# WASP-PCB-WDT-F1R0.net
KiCad netlist of a schematic drawn in EAGLE
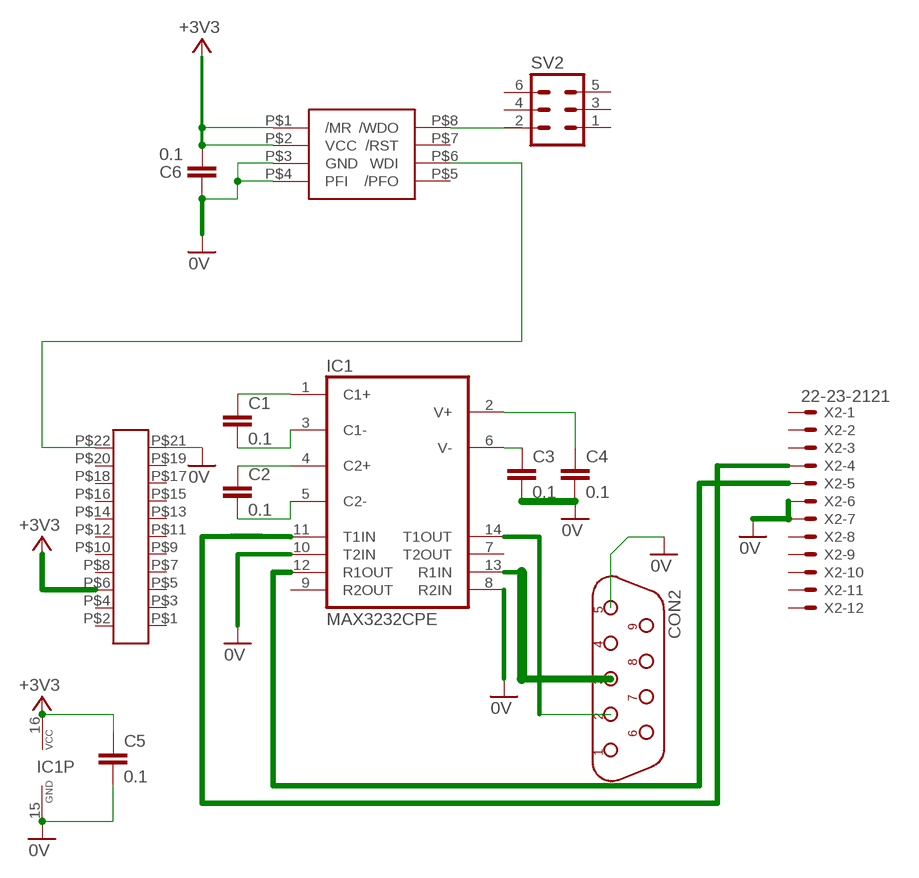
[diagram p0: schematic, sheet 1]

(export (version "E")
  (design (tool "Eeschema 10.0.6"))
  (components
    (comp (ref "C1")
      (value "0.1")
      (footprint "eagle-import:C5B2.5")
      (libsource (lib "eagle-import") (part "C5/2.5"))
    )
    (comp (ref "C2")
      (value "0.1")
      (footprint "eagle-import:C5B2.5")
      (libsource (lib "eagle-import") (part "C5/2.5"))
    )
    (comp (ref "C3")
      (value "0.1")
      (footprint "eagle-import:C5B2.5")
      (libsource (lib "eagle-import") (part "C5/2.5"))
    )
    (comp (ref "C4")
      (value "0.1")
      (footprint "eagle-import:C5B2.5")
      (libsource (lib "eagle-import") (part "C5/2.5"))
    )
    (comp (ref "C5")
      (value "0.1")
      (footprint "eagle-import:C5B2.5")
      (libsource (lib "eagle-import") (part "C5/2.5"))
    )
    (comp (ref "C6")
      (value "0.1")
      (footprint "eagle-import:C5B2.5")
      (libsource (lib "eagle-import") (part "C5/2.5"))
    )
    (comp (ref "CON2")
      (value "CONNECT_DB9F/90")
      (footprint "eagle-import:CONNECT_D-09F_90")
      (libsource (lib "eagle-import") (part "CONNECT_DB9F/90"))
    )
    (comp (ref "IC1")
      (value "MAX3232CPE")
      (footprint "eagle-import:DIL16")
      (fields (field (name "MF") "MAXIM") (field (name "MPN") "MAX3232CPE+"))
      (libsource (lib "eagle-import") (part "MAX3232PEC"))
    )
    (comp (ref "SV2")
      (value "CON-ML_ML6")
      (footprint "eagle-import:CON-ML_ML6")
      (libsource (lib "eagle-import") (part "CON-ML_ML6"))
    )
    (comp (ref "U$2")
      (value "ML22PML22P-PKG")
      (footprint "eagle-import:CON-ML-22P")
      (libsource (lib "eagle-import") (part "ML22PML22P-PKG"))
    )
    (comp (ref "U$3")
      (value "ADM706P")
      (footprint "eagle-import:ADM706P")
      (libsource (lib "eagle-import") (part "ADM706P"))
    )
    (comp (ref "X2")
      (value "22-23-2121")
      (footprint "eagle-import:22-23-2121")
      (fields (field (name "MF") "MOLEX"))
      (libsource (lib "eagle-import") (part "22-23-2121"))
    )
  )
  (nets
    (net (code "1") (name "+3V3") (class "Default")
      (node (ref "C5") (pin "1") (pinfunction "1_1") (pintype "passive"))
      (node (ref "C6") (pin "1") (pinfunction "1_1") (pintype "passive"))
      (node (ref "IC1") (pin "16") (pinfunction "VCC_16") (pintype "power_in"))
      (node (ref "U$2") (pin "P$6") (pinfunction "6_P$6") (pintype "passive"))
      (node (ref "U$3") (pin "P$1") (pinfunction "/MR_P$1") (pintype "input"))
      (node (ref "U$3") (pin "P$2") (pinfunction "VCC_P$2") (pintype "power_in"))
    )
    (net (code "2") (name "/14") (class "Default")
      (node (ref "U$2") (pin "P$14") (pinfunction "14_P$14") (pintype "power_in"))
    )
    (net (code "3") (name "0V") (class "Default")
      (node (ref "C3") (pin "2") (pinfunction "2_2") (pintype "passive"))
      (node (ref "C4") (pin "2") (pinfunction "2_2") (pintype "passive"))
      (node (ref "C5") (pin "2") (pinfunction "2_2") (pintype "passive"))
      (node (ref "C6") (pin "2") (pinfunction "2_2") (pintype "passive"))
      (node (ref "CON2") (pin "5") (pinfunction "5_5") (pintype "passive"))
      (node (ref "IC1") (pin "10") (pinfunction "T2IN_10") (pintype "input"))
      (node (ref "IC1") (pin "15") (pinfunction "GND_15") (pintype "power_in"))
      (node (ref "IC1") (pin "8") (pinfunction "R2IN_8") (pintype "input"))
      (node (ref "U$2") (pin "P$21") (pinfunction "21_P$21") (pintype "passive"))
      (node (ref "U$3") (pin "P$3") (pinfunction "GND_P$3") (pintype "power_in"))
      (node (ref "U$3") (pin "P$4") (pinfunction "PFI_P$4") (pintype "input"))
      (node (ref "X2") (pin "6") (pinfunction "S_6") (pintype "passive"))
      (node (ref "X2") (pin "7") (pinfunction "S_7") (pintype "passive"))
    )
    (net (code "4") (name "Net-(IC1A-C1+)") (class "Default")
      (node (ref "C1") (pin "1") (pinfunction "1_1") (pintype "passive"))
      (node (ref "IC1") (pin "1") (pinfunction "C1+_1") (pintype "bidirectional"))
    )
    (net (code "5") (name "Net-(IC1A-C1-)") (class "Default")
      (node (ref "C1") (pin "2") (pinfunction "2_2") (pintype "passive"))
      (node (ref "IC1") (pin "3") (pinfunction "C1-_3") (pintype "bidirectional"))
    )
    (net (code "6") (name "Net-(IC1A-C2+)") (class "Default")
      (node (ref "C2") (pin "1") (pinfunction "1_1") (pintype "passive"))
      (node (ref "IC1") (pin "4") (pinfunction "C2+_4") (pintype "bidirectional"))
    )
    (net (code "7") (name "Net-(IC1A-C2-)") (class "Default")
      (node (ref "C2") (pin "2") (pinfunction "2_2") (pintype "passive"))
      (node (ref "IC1") (pin "5") (pinfunction "C2-_5") (pintype "bidirectional"))
    )
    (net (code "8") (name "Net-(IC1A-R1IN)") (class "Default")
      (node (ref "CON2") (pin "3") (pinfunction "3_3") (pintype "passive"))
      (node (ref "IC1") (pin "13") (pinfunction "R1IN_13") (pintype "input"))
    )
    (net (code "9") (name "Net-(IC1A-R1OUT)") (class "Default")
      (node (ref "IC1") (pin "12") (pinfunction "R1OUT_12") (pintype "output"))
      (node (ref "X2") (pin "5") (pinfunction "S_5") (pintype "passive"))
    )
    (net (code "10") (name "Net-(IC1A-T1IN)") (class "Default")
      (node (ref "IC1") (pin "11") (pinfunction "T1IN_11") (pintype "input"))
      (node (ref "X2") (pin "4") (pinfunction "S_4") (pintype "passive"))
    )
    (net (code "11") (name "Net-(IC1A-T1OUT)") (class "Default")
      (node (ref "CON2") (pin "2") (pinfunction "2_2") (pintype "passive"))
      (node (ref "IC1") (pin "14") (pinfunction "T1OUT_14") (pintype "output"))
    )
    (net (code "12") (name "Net-(IC1A-V+)") (class "Default")
      (node (ref "C4") (pin "1") (pinfunction "1_1") (pintype "passive"))
      (node (ref "IC1") (pin "2") (pinfunction "V+_2") (pintype "bidirectional"))
    )
    (net (code "13") (name "Net-(IC1A-V-)") (class "Default")
      (node (ref "C3") (pin "1") (pinfunction "1_1") (pintype "passive"))
      (node (ref "IC1") (pin "6") (pinfunction "V-_6") (pintype "bidirectional"))
    )
    (net (code "14") (name "Net-(U$2-22)") (class "Default")
      (node (ref "U$2") (pin "P$22") (pinfunction "22_P$22") (pintype "passive"))
      (node (ref "U$3") (pin "P$6") (pinfunction "WDI_P$6") (pintype "input"))
    )
    (net (code "15") (name "Net-(U$3-{slash}WDO)") (class "Default")
      (node (ref "SV2") (pin "2") (pinfunction "2_2") (pintype "passive"))
      (node (ref "U$3") (pin "P$8") (pinfunction "/WDO_P$8") (pintype "output"))
    )
    (net (code "16") (name "unconnected-(CON2-Pad1)") (class "Default")
      (node (ref "CON2") (pin "1") (pinfunction "1_1") (pintype "passive"))
    )
    (net (code "17") (name "unconnected-(CON2-Pad4)") (class "Default")
      (node (ref "CON2") (pin "4") (pinfunction "4_4") (pintype "passive"))
    )
    (net (code "18") (name "unconnected-(CON2-Pad6)") (class "Default")
      (node (ref "CON2") (pin "6") (pinfunction "6_6") (pintype "passive"))
    )
    (net (code "19") (name "unconnected-(CON2-Pad7)") (class "Default")
      (node (ref "CON2") (pin "7") (pinfunction "7_7") (pintype "passive"))
    )
    (net (code "20") (name "unconnected-(CON2-Pad8)") (class "Default")
      (node (ref "CON2") (pin "8") (pinfunction "8_8") (pintype "passive"))
    )
    (net (code "21") (name "unconnected-(CON2-Pad9)") (class "Default")
      (node (ref "CON2") (pin "9") (pinfunction "9_9") (pintype "passive"))
    )
    (net (code "22") (name "unconnected-(IC1A-R2OUT-Pad9)") (class "Default")
      (node (ref "IC1") (pin "9") (pinfunction "R2OUT_9") (pintype "output"))
    )
    (net (code "23") (name "unconnected-(IC1A-T2OUT-Pad7)") (class "Default")
      (node (ref "IC1") (pin "7") (pinfunction "T2OUT_7") (pintype "output"))
    )
    (net (code "24") (name "unconnected-(SV2-Pad1)") (class "Default")
      (node (ref "SV2") (pin "1") (pinfunction "1_1") (pintype "passive"))
    )
    (net (code "25") (name "unconnected-(SV2-Pad3)") (class "Default")
      (node (ref "SV2") (pin "3") (pinfunction "3_3") (pintype "passive"))
    )
    (net (code "26") (name "unconnected-(SV2-Pad4)") (class "Default")
      (node (ref "SV2") (pin "4") (pinfunction "4_4") (pintype "passive"))
    )
    (net (code "27") (name "unconnected-(SV2-Pad5)") (class "Default")
      (node (ref "SV2") (pin "5") (pinfunction "5_5") (pintype "passive"))
    )
    (net (code "28") (name "unconnected-(SV2-Pad6)") (class "Default")
      (node (ref "SV2") (pin "6") (pinfunction "6_6") (pintype "passive"))
    )
    (net (code "29") (name "unconnected-(U$2-1-PadP$1)") (class "Default")
      (node (ref "U$2") (pin "P$1") (pinfunction "1_P$1") (pintype "passive"))
    )
    (net (code "30") (name "unconnected-(U$2-2-PadP$2)") (class "Default")
      (node (ref "U$2") (pin "P$2") (pinfunction "2_P$2") (pintype "passive"))
    )
    (net (code "31") (name "unconnected-(U$2-3-PadP$3)") (class "Default")
      (node (ref "U$2") (pin "P$3") (pinfunction "3_P$3") (pintype "passive"))
    )
    (net (code "32") (name "unconnected-(U$2-4-PadP$4)") (class "Default")
      (node (ref "U$2") (pin "P$4") (pinfunction "4_P$4") (pintype "passive"))
    )
    (net (code "33") (name "unconnected-(U$2-5-PadP$5)") (class "Default")
      (node (ref "U$2") (pin "P$5") (pinfunction "5_P$5") (pintype "passive"))
    )
    (net (code "34") (name "unconnected-(U$2-7-PadP$7)") (class "Default")
      (node (ref "U$2") (pin "P$7") (pinfunction "7_P$7") (pintype "passive"))
    )
    (net (code "35") (name "unconnected-(U$2-8-PadP$8)") (class "Default")
      (node (ref "U$2") (pin "P$8") (pinfunction "8_P$8") (pintype "passive"))
    )
    (net (code "36") (name "unconnected-(U$2-9-PadP$9)") (class "Default")
      (node (ref "U$2") (pin "P$9") (pinfunction "9_P$9") (pintype "passive"))
    )
    (net (code "37") (name "unconnected-(U$2-10-PadP$10)") (class "Default")
      (node (ref "U$2") (pin "P$10") (pinfunction "10_P$10") (pintype "passive"))
    )
    (net (code "38") (name "unconnected-(U$2-11-PadP$11)") (class "Default")
      (node (ref "U$2") (pin "P$11") (pinfunction "11_P$11") (pintype "passive"))
    )
    (net (code "39") (name "unconnected-(U$2-12-PadP$12)") (class "Default")
      (node (ref "U$2") (pin "P$12") (pinfunction "12_P$12") (pintype "passive"))
    )
    (net (code "40") (name "unconnected-(U$2-13-PadP$13)") (class "Default")
      (node (ref "U$2") (pin "P$13") (pinfunction "13_P$13") (pintype "passive"))
    )
    (net (code "41") (name "unconnected-(U$2-15-PadP$15)") (class "Default")
      (node (ref "U$2") (pin "P$15") (pinfunction "15_P$15") (pintype "passive"))
    )
    (net (code "42") (name "unconnected-(U$2-16-PadP$16)") (class "Default")
      (node (ref "U$2") (pin "P$16") (pinfunction "16_P$16") (pintype "passive"))
    )
    (net (code "43") (name "unconnected-(U$2-17-PadP$17)") (class "Default")
      (node (ref "U$2") (pin "P$17") (pinfunction "17_P$17") (pintype "passive"))
    )
    (net (code "44") (name "unconnected-(U$2-18-PadP$18)") (class "Default")
      (node (ref "U$2") (pin "P$18") (pinfunction "18_P$18") (pintype "passive"))
    )
    (net (code "45") (name "unconnected-(U$2-19-PadP$19)") (class "Default")
      (node (ref "U$2") (pin "P$19") (pinfunction "19_P$19") (pintype "passive"))
    )
    (net (code "46") (name "unconnected-(U$2-20-PadP$20)") (class "Default")
      (node (ref "U$2") (pin "P$20") (pinfunction "20_P$20") (pintype "passive"))
    )
    (net (code "47") (name "unconnected-(U$3-{slash}PFO-PadP$5)") (class "Default")
      (node (ref "U$3") (pin "P$5") (pinfunction "/PFO_P$5") (pintype "output"))
    )
    (net (code "48") (name "unconnected-(U$3-{slash}RST-PadP$7)") (class "Default")
      (node (ref "U$3") (pin "P$7") (pinfunction "/RST_P$7") (pintype "output"))
    )
    (net (code "49") (name "unconnected-(X2A-S-Pad1)") (class "Default")
      (node (ref "X2") (pin "1") (pinfunction "S_1") (pintype "passive"))
    )
    (net (code "50") (name "unconnected-(X2B-S-Pad10)") (class "Default")
      (node (ref "X2") (pin "10") (pinfunction "S_10") (pintype "passive"))
    )
    (net (code "51") (name "unconnected-(X2C-S-Pad11)") (class "Default")
      (node (ref "X2") (pin "11") (pinfunction "S_11") (pintype "passive"))
    )
    (net (code "52") (name "unconnected-(X2D-S-Pad12)") (class "Default")
      (node (ref "X2") (pin "12") (pinfunction "S_12") (pintype "passive"))
    )
    (net (code "53") (name "unconnected-(X2E-S-Pad2)") (class "Default")
      (node (ref "X2") (pin "2") (pinfunction "S_2") (pintype "passive"))
    )
    (net (code "54") (name "unconnected-(X2F-S-Pad3)") (class "Default")
      (node (ref "X2") (pin "3") (pinfunction "S_3") (pintype "passive"))
    )
    (net (code "55") (name "unconnected-(X2K-S-Pad8)") (class "Default")
      (node (ref "X2") (pin "8") (pinfunction "S_8") (pintype "passive"))
    )
    (net (code "56") (name "unconnected-(X2L-S-Pad9)") (class "Default")
      (node (ref "X2") (pin "9") (pinfunction "S_9") (pintype "passive"))
    )
  )
)
